# 3PDT_Board.net
KiCad netlist of a schematic drawn in EAGLE
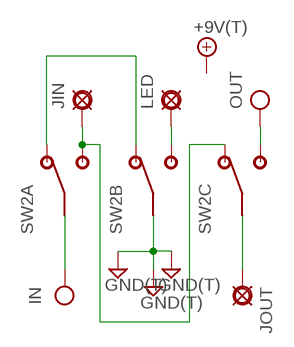
[diagram p0: schematic, sheet 1]

(export (version "E")
  (design (tool "Eeschema 10.0.6"))
  (components
    (comp (ref "+9V")
      (value "+9V(T)")
      (footprint "eagle-import:SQUARE")
      (libsource (lib "eagle-import") (part "+9V(T)"))
    )
    (comp (ref "G")
      (value "GND(T)")
      (footprint "eagle-import:SQUARE")
      (libsource (lib "eagle-import") (part "GND(T)"))
    )
    (comp (ref "IN")
      (value "IN(T)")
      (footprint "eagle-import:SQUARE")
      (libsource (lib "eagle-import") (part "IN(T)"))
    )
    (comp (ref "JIG")
      (value "GND(T)")
      (footprint "eagle-import:SQUARE")
      (libsource (lib "eagle-import") (part "GND(T)"))
    )
    (comp (ref "JIN")
      (value "PAD")
      (footprint "eagle-import:SQUARE")
      (libsource (lib "eagle-import") (part "PAD"))
    )
    (comp (ref "JOG")
      (value "GND(T)")
      (footprint "eagle-import:SQUARE")
      (libsource (lib "eagle-import") (part "GND(T)"))
    )
    (comp (ref "JOUT")
      (value "PAD")
      (footprint "eagle-import:SQUARE")
      (libsource (lib "eagle-import") (part "PAD"))
    )
    (comp (ref "LED")
      (value "PAD")
      (footprint "eagle-import:SQUARE")
      (libsource (lib "eagle-import") (part "PAD"))
    )
    (comp (ref "OUT")
      (value "OUT(T)")
      (footprint "eagle-import:SQUARE")
      (libsource (lib "eagle-import") (part "OUT(T)"))
    )
    (comp (ref "SW2")
      (value "3PDT")
      (footprint "eagle-import:3PDT")
      (libsource (lib "eagle-import") (part "3PDT"))
    )
  )
  (nets
    (net (code "1") (name "+9V(T)") (class "Default")
      (node (ref "+9V") (pin "1") (pinfunction "+9V_1") (pintype "power_in"))
    )
    (net (code "2") (name "GND(T)") (class "Default")
      (node (ref "G") (pin "1") (pinfunction "GND_1") (pintype "power_in"))
      (node (ref "JIG") (pin "1") (pinfunction "GND_1") (pintype "power_in"))
      (node (ref "JOG") (pin "1") (pinfunction "GND_1") (pintype "power_in"))
      (node (ref "SW2") (pin "B2") (pinfunction "2_B2") (pintype "passive"))
    )
    (net (code "3") (name "IN(T)") (class "Default")
      (node (ref "IN") (pin "1") (pinfunction "IN_1") (pintype "power_in"))
      (node (ref "SW2") (pin "A2") (pinfunction "2_A2") (pintype "passive"))
    )
    (net (code "4") (name "Net-(JIN-PAD)") (class "Default")
      (node (ref "JIN") (pin "1") (pinfunction "PAD_1") (pintype "passive"))
      (node (ref "SW2") (pin "A3") (pinfunction "3_A3") (pintype "passive"))
      (node (ref "SW2") (pin "C1") (pinfunction "1_C1") (pintype "passive"))
    )
    (net (code "5") (name "Net-(JOUT-PAD)") (class "Default")
      (node (ref "JOUT") (pin "1") (pinfunction "PAD_1") (pintype "passive"))
      (node (ref "SW2") (pin "C2") (pinfunction "2_C2") (pintype "passive"))
    )
    (net (code "6") (name "Net-(LED-PAD)") (class "Default")
      (node (ref "LED") (pin "1") (pinfunction "PAD_1") (pintype "passive"))
      (node (ref "SW2") (pin "B3") (pinfunction "3_B3") (pintype "passive"))
    )
    (net (code "7") (name "Net-(SW2A-1)") (class "Default")
      (node (ref "SW2") (pin "A1") (pinfunction "1_A1") (pintype "passive"))
      (node (ref "SW2") (pin "B1") (pinfunction "1_B1") (pintype "passive"))
    )
    (net (code "8") (name "OUT(T)") (class "Default")
      (node (ref "OUT") (pin "1") (pinfunction "OUT_1") (pintype "power_in"))
      (node (ref "SW2") (pin "C3") (pinfunction "3_C3") (pintype "passive"))
    )
  )
)
